# TH2.net
KiCad netlist of a schematic drawn in Altium Designer
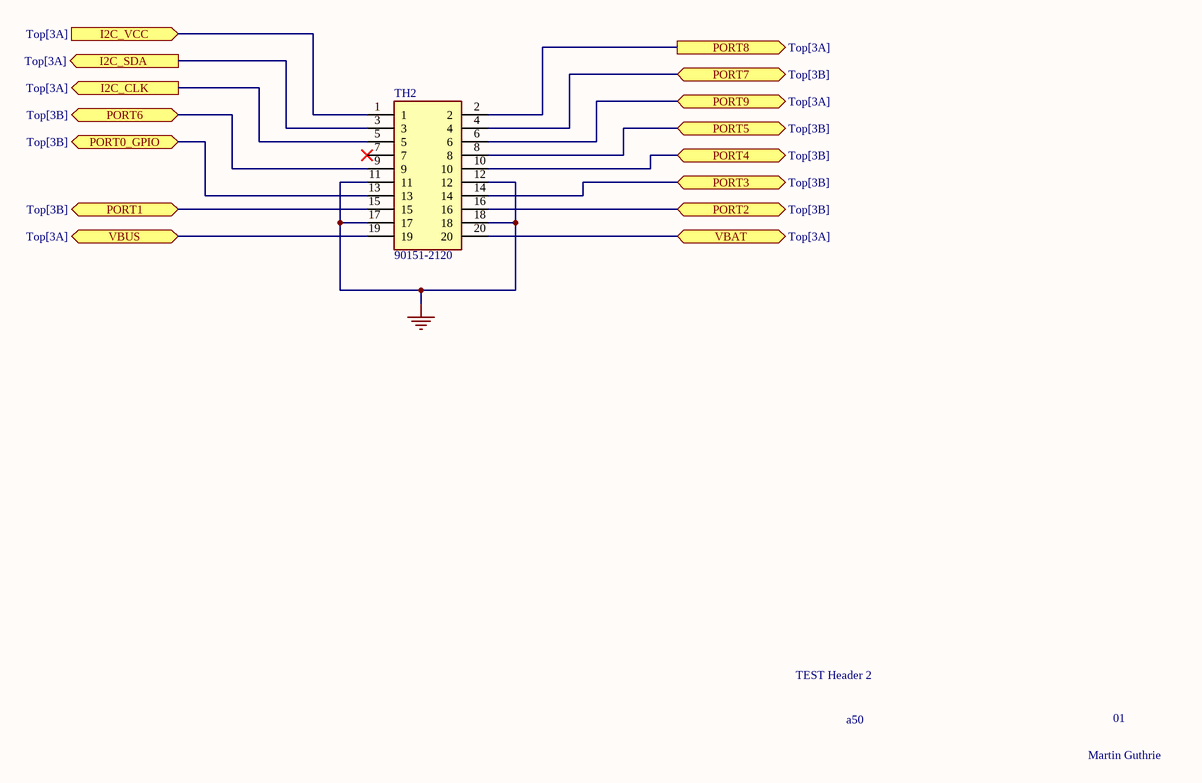
[diagram p0: TH2.SchDoc]

(export (version "E")
  (design (tool "Eeschema 10.0.6"))
  (components
    (comp (ref "TH2")
      (value "90151-2120")
      (footprint "PcbLib:90151-2120")
      (description "Connector")
      (fields (field (name "MOUSER PART NUMBER") "538-90151-2120"))
      (libsource (lib "SchematicLib") (part "90151-2120"))
    )
  )
  (nets
    (net (code "1") (name "/I2C_CLK") (class "Default")
      (node (ref "TH2") (pin "5") (pinfunction "5_5") (pintype "passive"))
    )
    (net (code "2") (name "/I2C_SDA") (class "Default")
      (node (ref "TH2") (pin "3") (pinfunction "3_3") (pintype "passive"))
    )
    (net (code "3") (name "/I2C_VCC") (class "Default")
      (node (ref "TH2") (pin "1") (pinfunction "1_1") (pintype "passive"))
    )
    (net (code "4") (name "/PORT0_GPIO") (class "Default")
      (node (ref "TH2") (pin "13") (pinfunction "13_13") (pintype "passive"))
    )
    (net (code "5") (name "/PORT1") (class "Default")
      (node (ref "TH2") (pin "15") (pinfunction "15_15") (pintype "passive"))
    )
    (net (code "6") (name "/PORT2") (class "Default")
      (node (ref "TH2") (pin "16") (pinfunction "16_16") (pintype "passive"))
    )
    (net (code "7") (name "/PORT3") (class "Default")
      (node (ref "TH2") (pin "14") (pinfunction "14_14") (pintype "passive"))
    )
    (net (code "8") (name "/PORT4") (class "Default")
      (node (ref "TH2") (pin "10") (pinfunction "10_10") (pintype "passive"))
    )
    (net (code "9") (name "/PORT5") (class "Default")
      (node (ref "TH2") (pin "8") (pinfunction "8_8") (pintype "passive"))
    )
    (net (code "10") (name "/PORT6") (class "Default")
      (node (ref "TH2") (pin "9") (pinfunction "9_9") (pintype "passive"))
    )
    (net (code "11") (name "/PORT7") (class "Default")
      (node (ref "TH2") (pin "4") (pinfunction "4_4") (pintype "passive"))
    )
    (net (code "12") (name "/PORT8") (class "Default")
      (node (ref "TH2") (pin "2") (pinfunction "2_2") (pintype "passive"))
    )
    (net (code "13") (name "/PORT9") (class "Default")
      (node (ref "TH2") (pin "6") (pinfunction "6_6") (pintype "passive"))
    )
    (net (code "14") (name "/VBAT") (class "Default")
      (node (ref "TH2") (pin "20") (pinfunction "20_20") (pintype "passive"))
    )
    (net (code "15") (name "/VBUS") (class "Default")
      (node (ref "TH2") (pin "19") (pinfunction "19_19") (pintype "passive"))
    )
    (net (code "16") (name "GND") (class "Default")
      (node (ref "TH2") (pin "11") (pinfunction "11_11") (pintype "passive"))
      (node (ref "TH2") (pin "12") (pinfunction "12_12") (pintype "passive"))
      (node (ref "TH2") (pin "17") (pinfunction "17_17") (pintype "passive"))
      (node (ref "TH2") (pin "18") (pinfunction "18_18") (pintype "passive"))
    )
    (net (code "17") (name "unconnected-(TH2-Pad7)") (class "Default")
      (node (ref "TH2") (pin "7") (pinfunction "7_7") (pintype "passive+no_connect"))
    )
  )
)
